# MA700.net
KiCad netlist of a schematic drawn in EAGLE
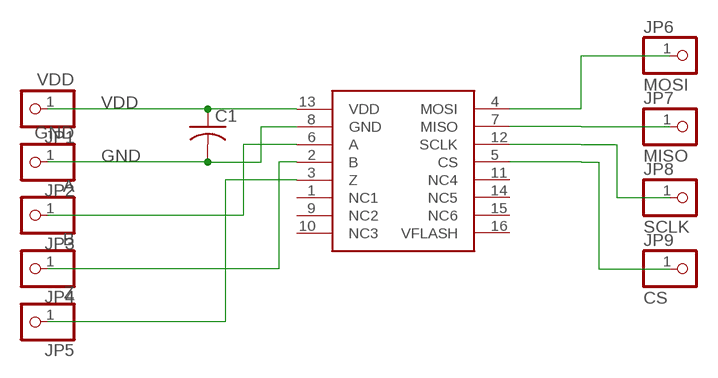
[diagram p0: schematic, sheet 1]

(export (version "E")
  (design (tool "Eeschema 10.0.6"))
  (components
    (comp (ref "C1")
      (value "C-USC0603")
      (footprint "eagle-import:C0603")
      (libsource (lib "eagle-import") (part "C-USC0603"))
    )
    (comp (ref "JP1")
      (value "VDD")
      (footprint "eagle-import:1X01")
      (libsource (lib "eagle-import") (part "PINHD-1X1"))
    )
    (comp (ref "JP2")
      (value "GND")
      (footprint "eagle-import:1X01")
      (libsource (lib "eagle-import") (part "PINHD-1X1"))
    )
    (comp (ref "JP3")
      (value "A")
      (footprint "eagle-import:1X01")
      (libsource (lib "eagle-import") (part "PINHD-1X1"))
    )
    (comp (ref "JP4")
      (value "B")
      (footprint "eagle-import:1X01")
      (libsource (lib "eagle-import") (part "PINHD-1X1"))
    )
    (comp (ref "JP5")
      (value "Z")
      (footprint "eagle-import:1X01")
      (libsource (lib "eagle-import") (part "PINHD-1X1"))
    )
    (comp (ref "JP6")
      (value "MOSI")
      (footprint "eagle-import:1X01")
      (libsource (lib "eagle-import") (part "PINHD-1X1"))
    )
    (comp (ref "JP7")
      (value "MISO")
      (footprint "eagle-import:1X01")
      (libsource (lib "eagle-import") (part "PINHD-1X1"))
    )
    (comp (ref "JP8")
      (value "SCLK")
      (footprint "eagle-import:1X01")
      (libsource (lib "eagle-import") (part "PINHD-1X1"))
    )
    (comp (ref "JP9")
      (value "CS")
      (footprint "eagle-import:1X01")
      (libsource (lib "eagle-import") (part "PINHD-1X1"))
    )
    (comp (ref "U$1")
      (value "MA700")
      (footprint "eagle-import:QFN16")
      (libsource (lib "eagle-import") (part "MA700"))
    )
  )
  (nets
    (net (code "1") (name "/GND") (class "Default")
      (node (ref "C1") (pin "2") (pinfunction "2_2") (pintype "passive"))
      (node (ref "JP2") (pin "1") (pinfunction "1_1") (pintype "passive"))
      (node (ref "U$1") (pin "8") (pinfunction "GND_8") (pintype "bidirectional"))
    )
    (net (code "2") (name "/VDD") (class "Default")
      (node (ref "C1") (pin "1") (pinfunction "1_1") (pintype "passive"))
      (node (ref "JP1") (pin "1") (pinfunction "1_1") (pintype "passive"))
      (node (ref "U$1") (pin "13") (pinfunction "VDD_13") (pintype "bidirectional"))
    )
    (net (code "3") (name "Net-(U$1-A)") (class "Default")
      (node (ref "JP3") (pin "1") (pinfunction "1_1") (pintype "passive"))
      (node (ref "U$1") (pin "6") (pinfunction "A_6") (pintype "bidirectional"))
    )
    (net (code "4") (name "Net-(U$1-B)") (class "Default")
      (node (ref "JP4") (pin "1") (pinfunction "1_1") (pintype "passive"))
      (node (ref "U$1") (pin "2") (pinfunction "B_2") (pintype "bidirectional"))
    )
    (net (code "5") (name "Net-(U$1-CS)") (class "Default")
      (node (ref "JP9") (pin "1") (pinfunction "1_1") (pintype "passive"))
      (node (ref "U$1") (pin "5") (pinfunction "CS_5") (pintype "bidirectional"))
    )
    (net (code "6") (name "Net-(U$1-MISO)") (class "Default")
      (node (ref "JP7") (pin "1") (pinfunction "1_1") (pintype "passive"))
      (node (ref "U$1") (pin "7") (pinfunction "MISO_7") (pintype "bidirectional"))
    )
    (net (code "7") (name "Net-(U$1-MOSI)") (class "Default")
      (node (ref "JP6") (pin "1") (pinfunction "1_1") (pintype "passive"))
      (node (ref "U$1") (pin "4") (pinfunction "MOSI_4") (pintype "bidirectional"))
    )
    (net (code "8") (name "Net-(U$1-SCLK)") (class "Default")
      (node (ref "JP8") (pin "1") (pinfunction "1_1") (pintype "passive"))
      (node (ref "U$1") (pin "12") (pinfunction "SCLK_12") (pintype "bidirectional"))
    )
    (net (code "9") (name "Net-(U$1-Z)") (class "Default")
      (node (ref "JP5") (pin "1") (pinfunction "1_1") (pintype "passive"))
      (node (ref "U$1") (pin "3") (pinfunction "Z_3") (pintype "bidirectional"))
    )
    (net (code "10") (name "unconnected-(U$1-NC1-Pad1)") (class "Default")
      (node (ref "U$1") (pin "1") (pinfunction "NC1_1") (pintype "bidirectional"))
    )
    (net (code "11") (name "unconnected-(U$1-NC2-Pad9)") (class "Default")
      (node (ref "U$1") (pin "9") (pinfunction "NC2_9") (pintype "bidirectional"))
    )
    (net (code "12") (name "unconnected-(U$1-NC3-Pad10)") (class "Default")
      (node (ref "U$1") (pin "10") (pinfunction "NC3_10") (pintype "bidirectional"))
    )
    (net (code "13") (name "unconnected-(U$1-NC4-Pad11)") (class "Default")
      (node (ref "U$1") (pin "11") (pinfunction "NC4_11") (pintype "bidirectional"))
    )
    (net (code "14") (name "unconnected-(U$1-NC5-Pad14)") (class "Default")
      (node (ref "U$1") (pin "14") (pinfunction "NC5_14") (pintype "bidirectional"))
    )
    (net (code "15") (name "unconnected-(U$1-NC6-Pad15)") (class "Default")
      (node (ref "U$1") (pin "15") (pinfunction "NC6_15") (pintype "bidirectional"))
    )
    (net (code "16") (name "unconnected-(U$1-VFLASH-Pad16)") (class "Default")
      (node (ref "U$1") (pin "16") (pinfunction "VFLASH_16") (pintype "bidirectional"))
    )
  )
)
